# vbat_board.net
KiCad netlist of a schematic drawn in EAGLE
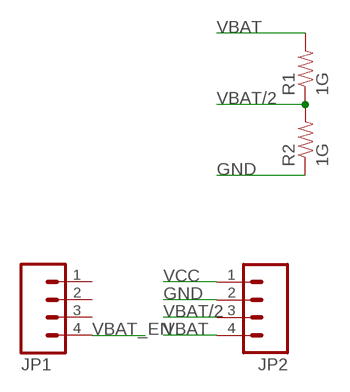
[diagram p0: schematic, sheet 1]

(export (version "E")
  (design (tool "Eeschema 10.0.6"))
  (components
    (comp (ref "JP1")
      (value "M04PTH")
      (footprint "eagle-import:1X04")
      (libsource (lib "eagle-import") (part "M04PTH"))
    )
    (comp (ref "JP2")
      (value "M04PTH")
      (footprint "eagle-import:1X04")
      (libsource (lib "eagle-import") (part "M04PTH"))
    )
    (comp (ref "R1")
      (value "1G")
      (footprint "eagle-import:AXIAL-0.3")
      (libsource (lib "eagle-import") (part "RESISTORAXIAL-0.3"))
    )
    (comp (ref "R2")
      (value "1G")
      (footprint "eagle-import:AXIAL-0.3")
      (libsource (lib "eagle-import") (part "RESISTORAXIAL-0.3"))
    )
  )
  (nets
    (net (code "1") (name "/GND") (class "Default")
      (node (ref "JP2") (pin "2") (pinfunction "2_2") (pintype "passive"))
      (node (ref "R2") (pin "P$1") (pinfunction "1_P$1") (pintype "passive"))
    )
    (net (code "2") (name "/VBAT") (class "Default")
      (node (ref "JP2") (pin "4") (pinfunction "4_4") (pintype "passive"))
      (node (ref "R1") (pin "P$2") (pinfunction "2_P$2") (pintype "passive"))
    )
    (net (code "3") (name "/VBAT_EN") (class "Default")
      (node (ref "JP1") (pin "4") (pinfunction "4_4") (pintype "passive"))
    )
    (net (code "4") (name "/VBAT{slash}2") (class "Default")
      (node (ref "JP2") (pin "3") (pinfunction "3_3") (pintype "passive"))
      (node (ref "R1") (pin "P$1") (pinfunction "1_P$1") (pintype "passive"))
      (node (ref "R2") (pin "P$2") (pinfunction "2_P$2") (pintype "passive"))
    )
    (net (code "5") (name "/VCC") (class "Default")
      (node (ref "JP2") (pin "1") (pinfunction "1_1") (pintype "passive"))
    )
    (net (code "6") (name "unconnected-(JP1-Pad1)") (class "Default")
      (node (ref "JP1") (pin "1") (pinfunction "1_1") (pintype "passive"))
    )
    (net (code "7") (name "unconnected-(JP1-Pad2)") (class "Default")
      (node (ref "JP1") (pin "2") (pinfunction "2_2") (pintype "passive"))
    )
    (net (code "8") (name "unconnected-(JP1-Pad3)") (class "Default")
      (node (ref "JP1") (pin "3") (pinfunction "3_3") (pintype "passive"))
    )
  )
)
